# main.net
KiCad netlist of a schematic drawn in EAGLE
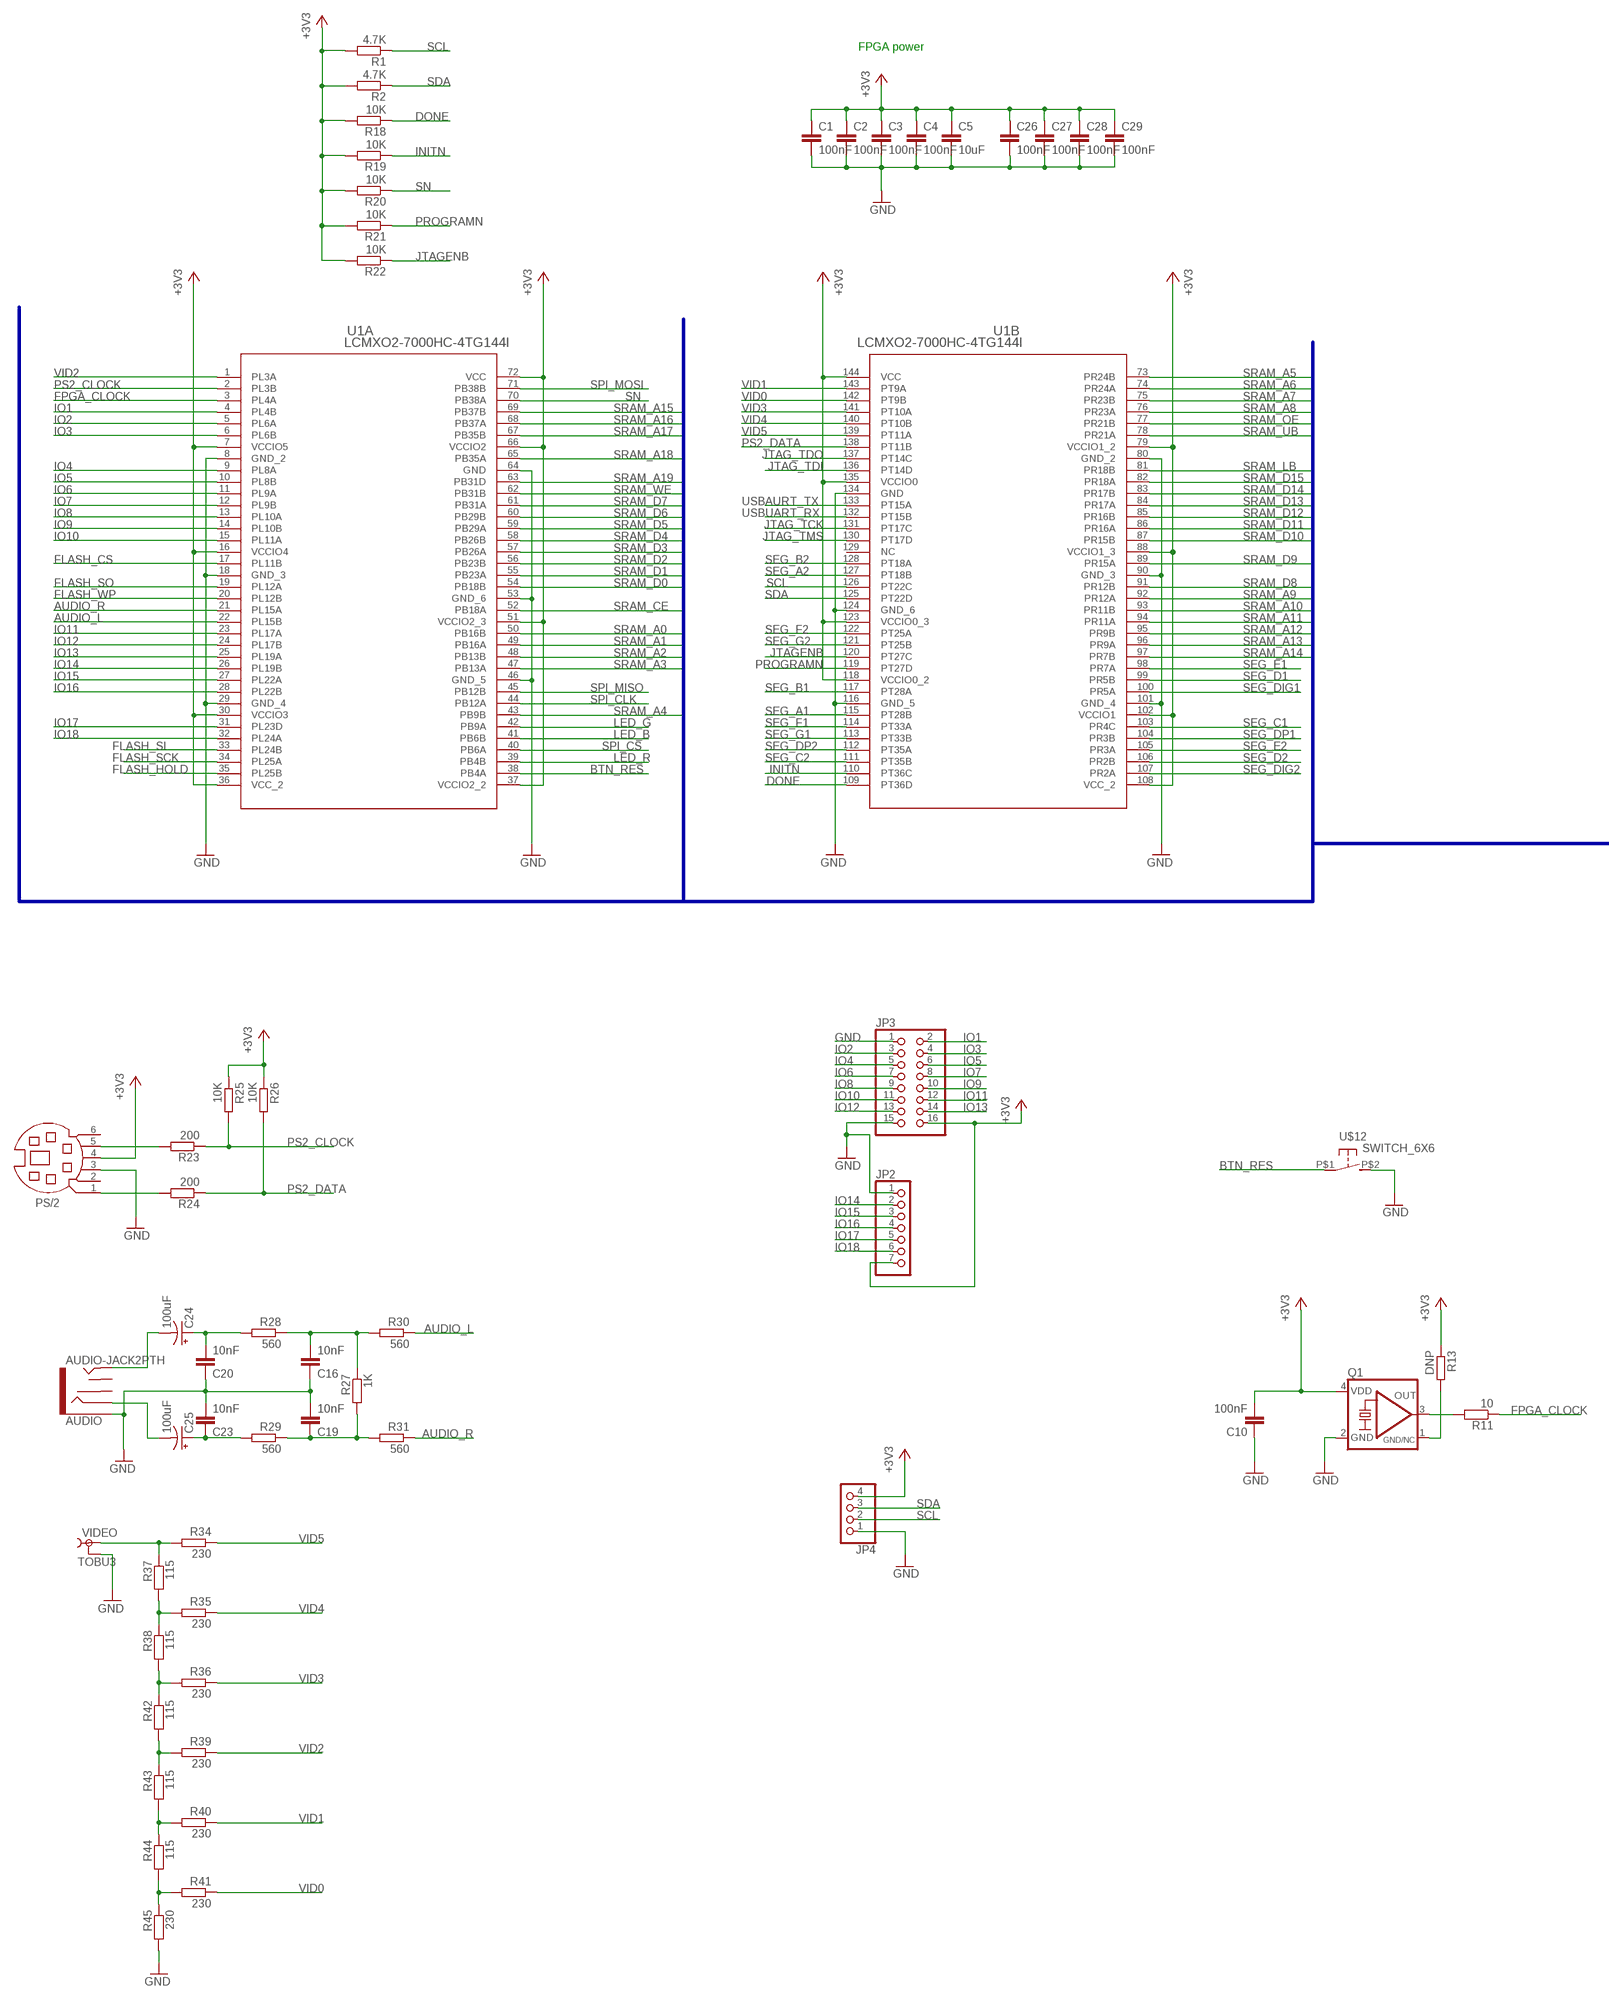
[diagram p0: schematic, sheet 1, part 1 of 2]
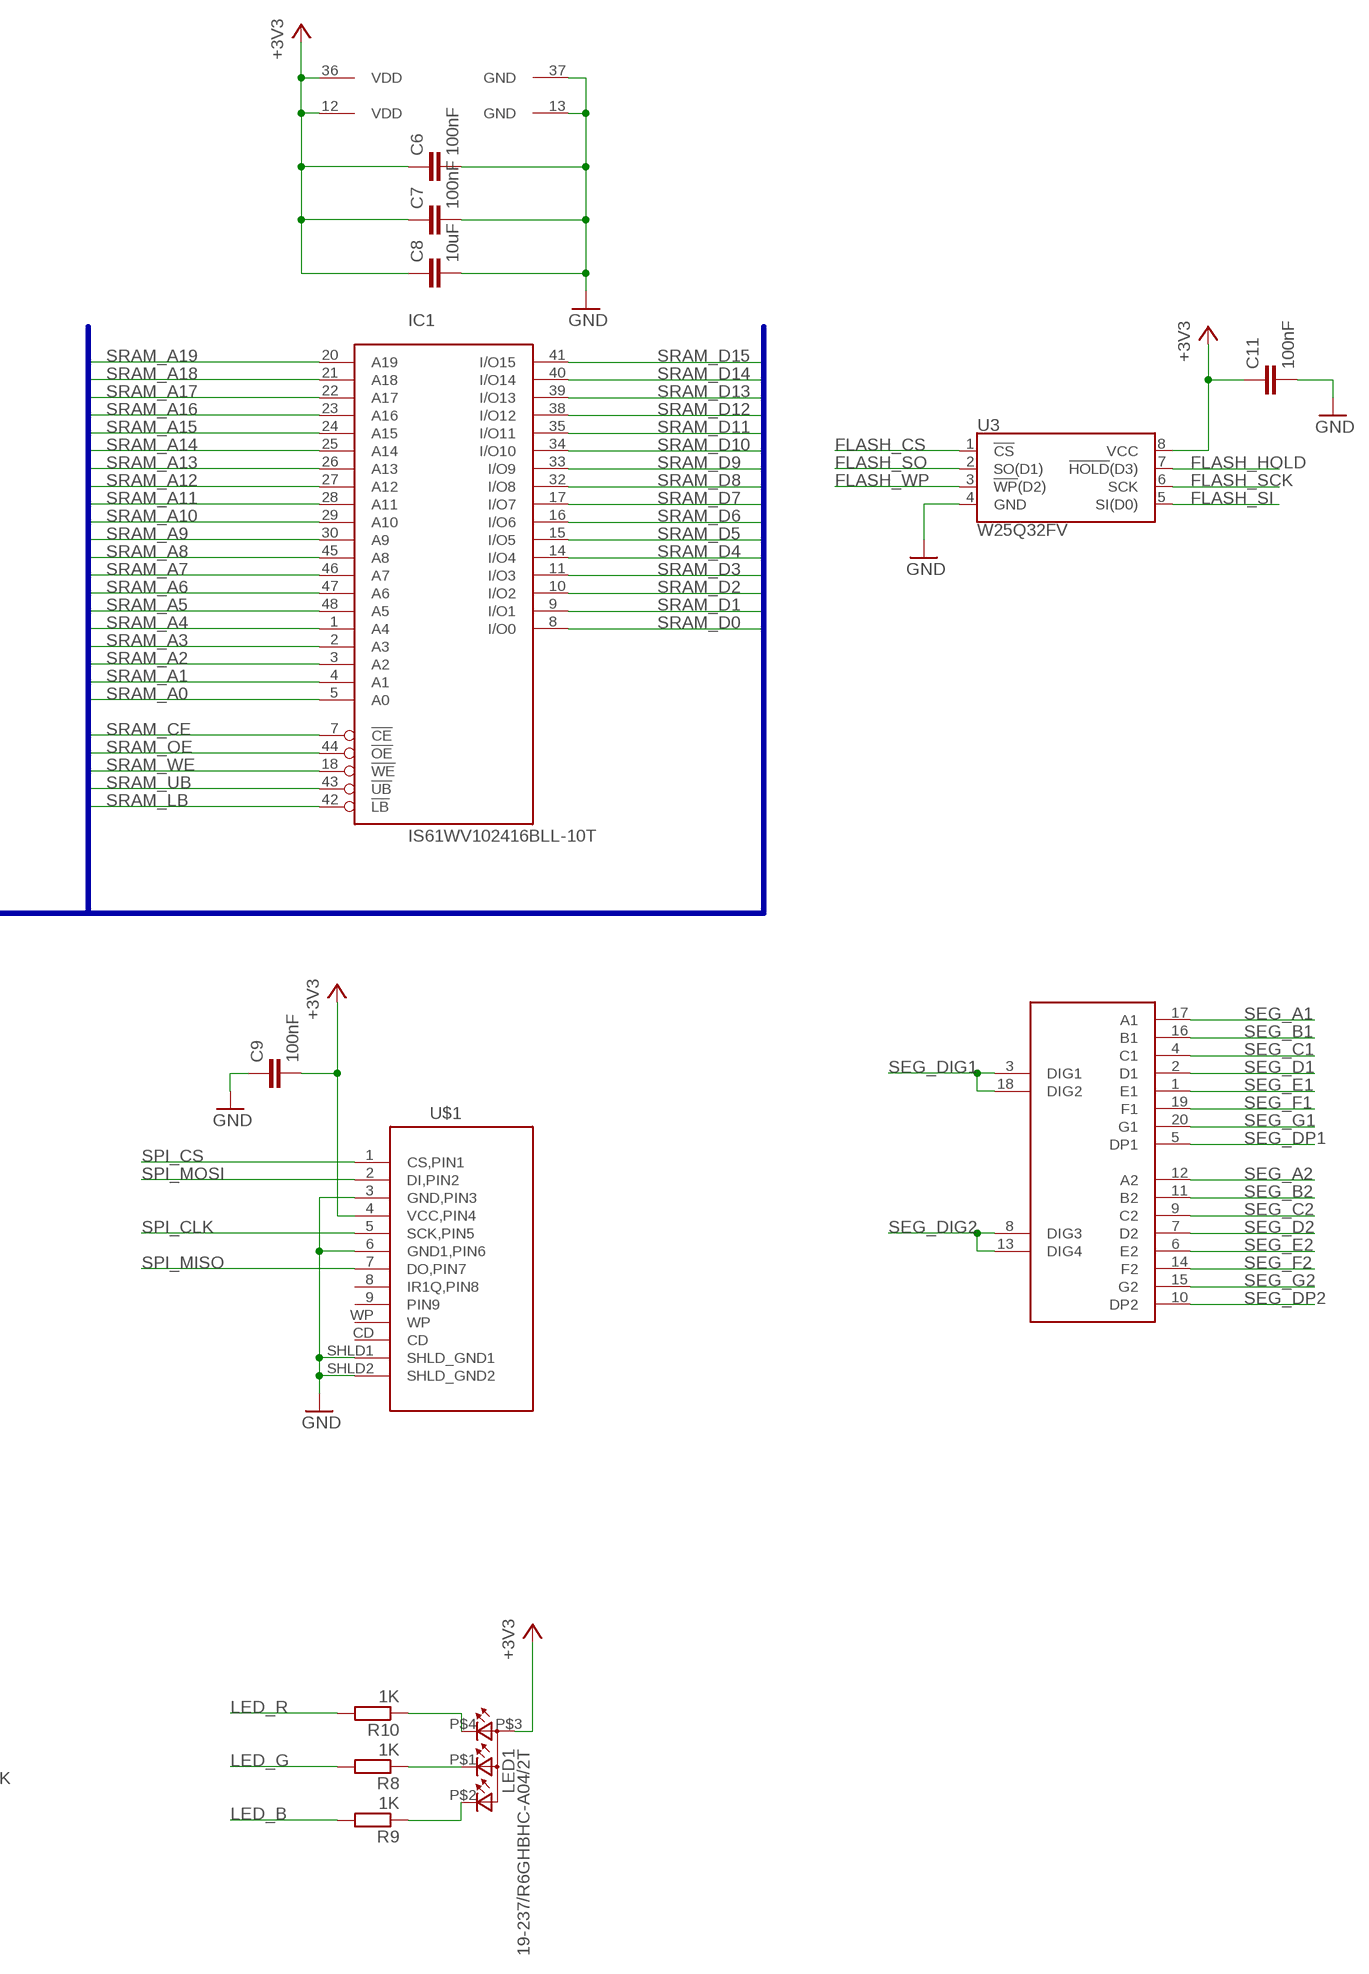
[diagram p1: schematic, sheet 1, part 2 of 2]
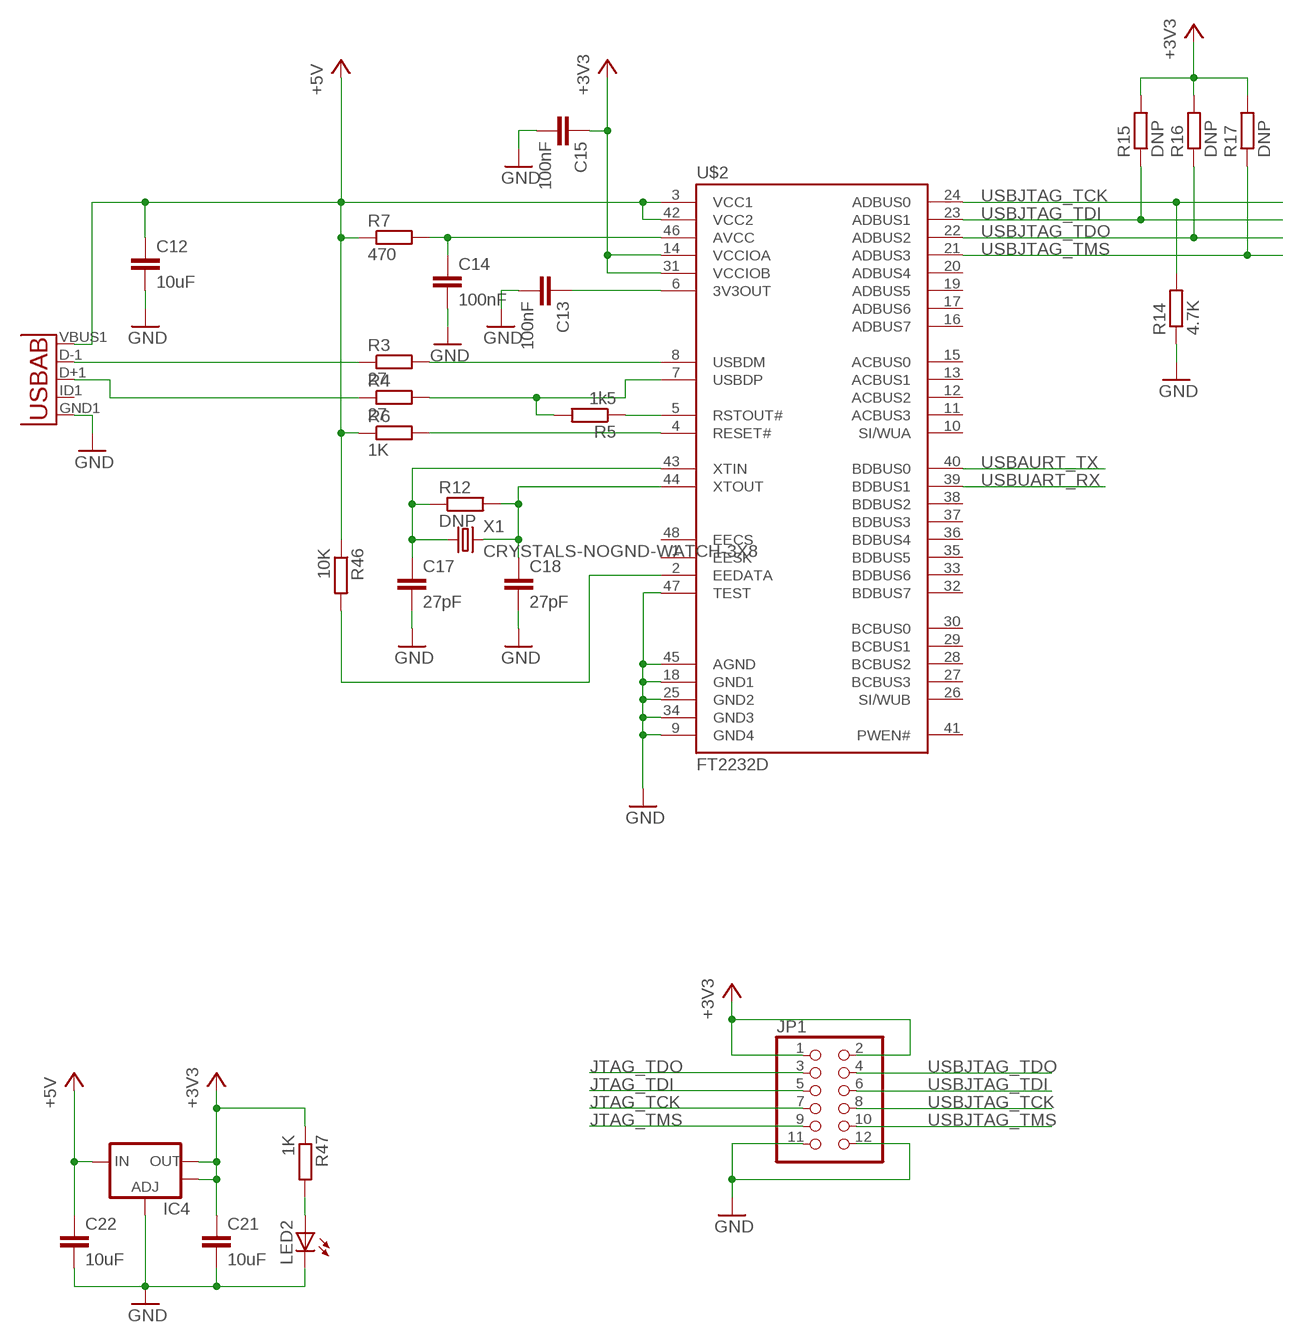
[diagram p2: schematic, sheet 2]

(export (version "E")
  (design (tool "Eeschema 10.0.6"))
  (components
    (comp (ref "AUDIO")
      (value "AUDIO-JACK2PTH")
      (footprint "eagle-import:AUDIO-JACK")
      (libsource (lib "eagle-import") (part "AUDIO-JACK2PTH"))
    )
    (comp (ref "C1")
      (value "100nF")
      (footprint "eagle-import:C0603")
      (libsource (lib "eagle-import") (part "C-EUC0603"))
    )
    (comp (ref "C2")
      (value "100nF")
      (footprint "eagle-import:C0603")
      (libsource (lib "eagle-import") (part "C-EUC0603"))
    )
    (comp (ref "C3")
      (value "100nF")
      (footprint "eagle-import:C0603")
      (libsource (lib "eagle-import") (part "C-EUC0603"))
    )
    (comp (ref "C4")
      (value "100nF")
      (footprint "eagle-import:C0603")
      (libsource (lib "eagle-import") (part "C-EUC0603"))
    )
    (comp (ref "C5")
      (value "10uF")
      (footprint "eagle-import:C0805")
      (libsource (lib "eagle-import") (part "C-EUC0805"))
    )
    (comp (ref "C6")
      (value "100nF")
      (footprint "eagle-import:C0603")
      (libsource (lib "eagle-import") (part "C-EUC0603"))
    )
    (comp (ref "C7")
      (value "100nF")
      (footprint "eagle-import:C0603")
      (libsource (lib "eagle-import") (part "C-EUC0603"))
    )
    (comp (ref "C8")
      (value "10uF")
      (footprint "eagle-import:C0805")
      (libsource (lib "eagle-import") (part "C-EUC0805"))
    )
    (comp (ref "C9")
      (value "100nF")
      (footprint "eagle-import:C0603")
      (libsource (lib "eagle-import") (part "C-EUC0603"))
    )
    (comp (ref "C10")
      (value "100nF")
      (footprint "eagle-import:C0603")
      (libsource (lib "eagle-import") (part "C-EUC0603"))
    )
    (comp (ref "C11")
      (value "100nF")
      (footprint "eagle-import:C0603")
      (libsource (lib "eagle-import") (part "C-EUC0603"))
    )
    (comp (ref "C16")
      (value "10nF")
      (footprint "eagle-import:C0603")
      (libsource (lib "eagle-import") (part "C-EUC0603"))
    )
    (comp (ref "C19")
      (value "10nF")
      (footprint "eagle-import:C0603")
      (libsource (lib "eagle-import") (part "C-EUC0603"))
    )
    (comp (ref "C20")
      (value "10nF")
      (footprint "eagle-import:C0603")
      (libsource (lib "eagle-import") (part "C-EUC0603"))
    )
    (comp (ref "C23")
      (value "10nF")
      (footprint "eagle-import:C0603")
      (libsource (lib "eagle-import") (part "C-EUC0603"))
    )
    (comp (ref "C24")
      (value "100uF")
      (footprint "eagle-import:EIA7343")
      (libsource (lib "eagle-import") (part "CAP_POL7343"))
    )
    (comp (ref "C25")
      (value "100uF")
      (footprint "eagle-import:EIA7343")
      (libsource (lib "eagle-import") (part "CAP_POL7343"))
    )
    (comp (ref "C26")
      (value "100nF")
      (footprint "eagle-import:C0603")
      (libsource (lib "eagle-import") (part "C-EUC0603"))
    )
    (comp (ref "C27")
      (value "100nF")
      (footprint "eagle-import:C0603")
      (libsource (lib "eagle-import") (part "C-EUC0603"))
    )
    (comp (ref "C28")
      (value "100nF")
      (footprint "eagle-import:C0603")
      (libsource (lib "eagle-import") (part "C-EUC0603"))
    )
    (comp (ref "C29")
      (value "100nF")
      (footprint "eagle-import:C0603")
      (libsource (lib "eagle-import") (part "C-EUC0603"))
    )
    (comp (ref "IC1")
      (value "IS61WV102416BLL-10T")
      (footprint "eagle-import:TSOP-I-48-12X40MM")
      (libsource (lib "eagle-import") (part "IS61WV102416BLL-T10"))
    )
    (comp (ref "JP2")
      (value "PINHD-1X7")
      (footprint "eagle-import:1X07")
      (libsource (lib "eagle-import") (part "PINHD-1X7"))
    )
    (comp (ref "JP3")
      (value "PINHD-2X8")
      (footprint "eagle-import:2X08")
      (libsource (lib "eagle-import") (part "PINHD-2X8"))
    )
    (comp (ref "JP4")
      (value "PINHD-1X4")
      (footprint "eagle-import:1X04")
      (libsource (lib "eagle-import") (part "PINHD-1X4"))
    )
    (comp (ref "LED1")
      (value "19-237/R6GHBHC-A04/2T")
      (footprint "eagle-import:19-237_R6GHBHC-A04_2T")
      (libsource (lib "eagle-import") (part "19-237/R6GHBHC-A04/2T"))
    )
    (comp (ref "PS/2")
      (value "MD06SS")
      (footprint "eagle-import:MDIN06SS")
      (libsource (lib "eagle-import") (part "MD06SS"))
    )
    (comp (ref "Q1")
      (value "KXO-TCXO-CMOS-82")
      (footprint "eagle-import:7.0X5.0_KXO-82-TCXO")
      (libsource (lib "eagle-import") (part "KXO-TCXO-CMOS-82"))
    )
    (comp (ref "R1")
      (value "4.7K")
      (footprint "eagle-import:R0603")
      (libsource (lib "eagle-import") (part "R-EU_R0603"))
    )
    (comp (ref "R2")
      (value "4.7K")
      (footprint "eagle-import:R0603")
      (libsource (lib "eagle-import") (part "R-EU_R0603"))
    )
    (comp (ref "R8")
      (value "1K")
      (footprint "eagle-import:R0603")
      (libsource (lib "eagle-import") (part "R-EU_R0603"))
    )
    (comp (ref "R9")
      (value "1K")
      (footprint "eagle-import:R0603")
      (libsource (lib "eagle-import") (part "R-EU_R0603"))
    )
    (comp (ref "R10")
      (value "1K")
      (footprint "eagle-import:R0603")
      (libsource (lib "eagle-import") (part "R-EU_R0603"))
    )
    (comp (ref "R11")
      (value "10")
      (footprint "eagle-import:R0603")
      (libsource (lib "eagle-import") (part "R-EU_R0603"))
    )
    (comp (ref "R13")
      (value "DNP")
      (footprint "eagle-import:R0603")
      (libsource (lib "eagle-import") (part "R-EU_R0603"))
    )
    (comp (ref "R18")
      (value "10K")
      (footprint "eagle-import:R0603")
      (libsource (lib "eagle-import") (part "R-EU_R0603"))
    )
    (comp (ref "R19")
      (value "10K")
      (footprint "eagle-import:R0603")
      (libsource (lib "eagle-import") (part "R-EU_R0603"))
    )
    (comp (ref "R20")
      (value "10K")
      (footprint "eagle-import:R0603")
      (libsource (lib "eagle-import") (part "R-EU_R0603"))
    )
    (comp (ref "R21")
      (value "10K")
      (footprint "eagle-import:R0603")
      (libsource (lib "eagle-import") (part "R-EU_R0603"))
    )
    (comp (ref "R22")
      (value "10K")
      (footprint "eagle-import:R0603")
      (libsource (lib "eagle-import") (part "R-EU_R0603"))
    )
    (comp (ref "R23")
      (value "200")
      (footprint "eagle-import:R0603")
      (libsource (lib "eagle-import") (part "R-EU_R0603"))
    )
    (comp (ref "R24")
      (value "200")
      (footprint "eagle-import:R0603")
      (libsource (lib "eagle-import") (part "R-EU_R0603"))
    )
    (comp (ref "R25")
      (value "10K")
      (footprint "eagle-import:R0603")
      (libsource (lib "eagle-import") (part "R-EU_R0603"))
    )
    (comp (ref "R26")
      (value "10K")
      (footprint "eagle-import:R0603")
      (libsource (lib "eagle-import") (part "R-EU_R0603"))
    )
    (comp (ref "R27")
      (value "1K")
      (footprint "eagle-import:R0603")
      (libsource (lib "eagle-import") (part "R-EU_R0603"))
    )
    (comp (ref "R28")
      (value "560")
      (footprint "eagle-import:R0603")
      (libsource (lib "eagle-import") (part "R-EU_R0603"))
    )
    (comp (ref "R29")
      (value "560")
      (footprint "eagle-import:R0603")
      (libsource (lib "eagle-import") (part "R-EU_R0603"))
    )
    (comp (ref "R30")
      (value "560")
      (footprint "eagle-import:R0603")
      (libsource (lib "eagle-import") (part "R-EU_R0603"))
    )
    (comp (ref "R31")
      (value "560")
      (footprint "eagle-import:R0603")
      (libsource (lib "eagle-import") (part "R-EU_R0603"))
    )
    (comp (ref "R34")
      (value "230")
      (footprint "eagle-import:R0603")
      (libsource (lib "eagle-import") (part "R-EU_R0603"))
    )
    (comp (ref "R35")
      (value "230")
      (footprint "eagle-import:R0603")
      (libsource (lib "eagle-import") (part "R-EU_R0603"))
    )
    (comp (ref "R36")
      (value "230")
      (footprint "eagle-import:R0603")
      (libsource (lib "eagle-import") (part "R-EU_R0603"))
    )
    (comp (ref "R37")
      (value "115")
      (footprint "eagle-import:R0603")
      (libsource (lib "eagle-import") (part "R-EU_R0603"))
    )
    (comp (ref "R38")
      (value "115")
      (footprint "eagle-import:R0603")
      (libsource (lib "eagle-import") (part "R-EU_R0603"))
    )
    (comp (ref "R39")
      (value "230")
      (footprint "eagle-import:R0603")
      (libsource (lib "eagle-import") (part "R-EU_R0603"))
    )
    (comp (ref "R40")
      (value "230")
      (footprint "eagle-import:R0603")
      (libsource (lib "eagle-import") (part "R-EU_R0603"))
    )
    (comp (ref "R41")
      (value "230")
      (footprint "eagle-import:R0603")
      (libsource (lib "eagle-import") (part "R-EU_R0603"))
    )
    (comp (ref "R42")
      (value "115")
      (footprint "eagle-import:R0603")
      (libsource (lib "eagle-import") (part "R-EU_R0603"))
    )
    (comp (ref "R43")
      (value "115")
      (footprint "eagle-import:R0603")
      (libsource (lib "eagle-import") (part "R-EU_R0603"))
    )
    (comp (ref "R44")
      (value "115")
      (footprint "eagle-import:R0603")
      (libsource (lib "eagle-import") (part "R-EU_R0603"))
    )
    (comp (ref "R45")
      (value "230")
      (footprint "eagle-import:R0603")
      (libsource (lib "eagle-import") (part "R-EU_R0603"))
    )
    (comp (ref "U$1")
      (value "FCI_SD_SOCKET")
      (footprint "eagle-import:SD-MMC_SOCKET-PP")
      (fields (field (name "MF") "FCI") (field (name "MPN") "10067847-001RLF"))
      (libsource (lib "eagle-import") (part "FCI_SD_SOCKET"))
    )
    (comp (ref "U$3")
      (value "GS2020CR-G")
      (footprint "eagle-import:GS2020CR")
      (libsource (lib "eagle-import") (part "GS2020CR-G"))
    )
    (comp (ref "U$12")
      (value "SWITCH_6X6")
      (footprint "eagle-import:SWITCH_6X6")
      (libsource (lib "eagle-import") (part "SWITCH_6X6"))
    )
    (comp (ref "U1")
      (value "LCMXO2-7000HC-4TG144I")
      (footprint "eagle-import:TQFP144")
      (fields (field (name "MANUFACTURER_PART_NUMBER") "LCMXO27000HC4TG144I"))
      (libsource (lib "eagle-import") (part "LCMXO2-7000HC-4TG144I"))
    )
    (comp (ref "U3")
      (value "W25Q32FV")
      (footprint "eagle-import:SOIC-8")
      (libsource (lib "eagle-import") (part "W25Q32FVSS"))
    )
    (comp (ref "VIDEO")
      (value "TOBU3")
      (footprint "eagle-import:TOBU3")
      (fields (field (name "MF") "FARNELL") (field (name "MPN") "TOBU 3"))
      (libsource (lib "eagle-import") (part "TOBU3"))
    )
    (comp (ref "C12")
      (value "10uF")
      (footprint "eagle-import:C0805")
      (libsource (lib "eagle-import") (part "C-EUC0805"))
    )
    (comp (ref "C13")
      (value "100nF")
      (footprint "eagle-import:C0603")
      (libsource (lib "eagle-import") (part "C-EUC0603"))
    )
    (comp (ref "C14")
      (value "100nF")
      (footprint "eagle-import:C0603")
      (libsource (lib "eagle-import") (part "C-EUC0603"))
    )
    (comp (ref "C15")
      (value "100nF")
      (footprint "eagle-import:C0603")
      (libsource (lib "eagle-import") (part "C-EUC0603"))
    )
    (comp (ref "C17")
      (value "27pF")
      (footprint "eagle-import:C0603")
      (libsource (lib "eagle-import") (part "C-EUC0603"))
    )
    (comp (ref "C18")
      (value "27pF")
      (footprint "eagle-import:C0603")
      (libsource (lib "eagle-import") (part "C-EUC0603"))
    )
    (comp (ref "C21")
      (value "10uF")
      (footprint "eagle-import:C0805")
      (libsource (lib "eagle-import") (part "C-EUC0805"))
    )
    (comp (ref "C22")
      (value "10uF")
      (footprint "eagle-import:C0805")
      (libsource (lib "eagle-import") (part "C-EUC0805"))
    )
    (comp (ref "IC4")
      (value "V_REG_LM1117SOT223")
      (footprint "eagle-import:SOT223")
      (libsource (lib "eagle-import") (part "V_REG_LM1117SOT223"))
    )
    (comp (ref "JP1")
      (value "PINHD-2X6")
      (footprint "eagle-import:2X06")
      (libsource (lib "eagle-import") (part "PINHD-2X6"))
    )
    (comp (ref "LED2")
      (value "LEDCHIPLED_0603")
      (footprint "eagle-import:CHIPLED_0603")
      (libsource (lib "eagle-import") (part "LEDCHIPLED_0603"))
    )
    (comp (ref "R3")
      (value "27")
      (footprint "eagle-import:R0603")
      (libsource (lib "eagle-import") (part "R-EU_R0603"))
    )
    (comp (ref "R4")
      (value "27")
      (footprint "eagle-import:R0603")
      (libsource (lib "eagle-import") (part "R-EU_R0603"))
    )
    (comp (ref "R5")
      (value "1k5")
      (footprint "eagle-import:R0603")
      (libsource (lib "eagle-import") (part "R-EU_R0603"))
    )
    (comp (ref "R6")
      (value "1K")
      (footprint "eagle-import:R0603")
      (libsource (lib "eagle-import") (part "R-EU_R0603"))
    )
    (comp (ref "R7")
      (value "470")
      (footprint "eagle-import:R0603")
      (libsource (lib "eagle-import") (part "R-EU_R0603"))
    )
    (comp (ref "R12")
      (value "DNP")
      (footprint "eagle-import:R0603")
      (libsource (lib "eagle-import") (part "R-EU_R0603"))
    )
    (comp (ref "R14")
      (value "4.7K")
      (footprint "eagle-import:R0603")
      (libsource (lib "eagle-import") (part "R-EU_R0603"))
    )
    (comp (ref "R15")
      (value "DNP")
      (footprint "eagle-import:R0603")
      (libsource (lib "eagle-import") (part "R-EU_R0603"))
    )
    (comp (ref "R16")
      (value "DNP")
      (footprint "eagle-import:R0603")
      (libsource (lib "eagle-import") (part "R-EU_R0603"))
    )
    (comp (ref "R17")
      (value "DNP")
      (footprint "eagle-import:R0603")
      (libsource (lib "eagle-import") (part "R-EU_R0603"))
    )
    (comp (ref "R46")
      (value "10K")
      (footprint "eagle-import:R0603")
      (libsource (lib "eagle-import") (part "R-EU_R0603"))
    )
    (comp (ref "R47")
      (value "1K")
      (footprint "eagle-import:R0603")
      (libsource (lib "eagle-import") (part "R-EU_R0603"))
    )
    (comp (ref "U$2")
      (value "FT2232D")
      (footprint "eagle-import:LQFP-48")
      (libsource (lib "eagle-import") (part "FT2232D"))
    )
    (comp (ref "U2")
      (value "USB\"\"")
      (footprint "eagle-import:USB-MICRO-SMD")
      (libsource (lib "eagle-import") (part "USB{dblquote}{dblquote}"))
    )
    (comp (ref "X1")
      (value "CRYSTALS-NOGND-WATCH-3X8")
      (footprint "eagle-import:WATCH-3X8")
      (libsource (lib "eagle-import") (part "CRYSTALS-NOGND-WATCH-3X8"))
    )
  )
  (nets
    (net (code "1") (name "+3V3") (class "Default")
      (node (ref "C1") (pin "1") (pinfunction "1_1") (pintype "passive"))
      (node (ref "C10") (pin "2") (pinfunction "2_2") (pintype "passive"))
      (node (ref "C11") (pin "1") (pinfunction "1_1") (pintype "passive"))
      (node (ref "C15") (pin "1") (pinfunction "1_1") (pintype "passive"))
      (node (ref "C2") (pin "1") (pinfunction "1_1") (pintype "passive"))
      (node (ref "C21") (pin "1") (pinfunction "1_1") (pintype "passive"))
      (node (ref "C26") (pin "1") (pinfunction "1_1") (pintype "passive"))
      (node (ref "C27") (pin "1") (pinfunction "1_1") (pintype "passive"))
      (node (ref "C28") (pin "1") (pinfunction "1_1") (pintype "passive"))
      (node (ref "C29") (pin "1") (pinfunction "1_1") (pintype "passive"))
      (node (ref "C3") (pin "1") (pinfunction "1_1") (pintype "passive"))
      (node (ref "C4") (pin "1") (pinfunction "1_1") (pintype "passive"))
      (node (ref "C5") (pin "1") (pinfunction "1_1") (pintype "passive"))
      (node (ref "C6") (pin "1") (pinfunction "1_1") (pintype "passive"))
      (node (ref "C7") (pin "1") (pinfunction "1_1") (pintype "passive"))
      (node (ref "C8") (pin "1") (pinfunction "1_1") (pintype "passive"))
      (node (ref "C9") (pin "2") (pinfunction "2_2") (pintype "passive"))
      (node (ref "IC1") (pin "12") (pinfunction "VDD_12") (pintype "power_in"))
      (node (ref "IC1") (pin "36") (pinfunction "VDD_36") (pintype "power_in"))
      (node (ref "IC4") (pin "2") (pinfunction "OUT_2") (pintype "output"))
      (node (ref "IC4") (pin "4") (pinfunction "OUT_4") (pintype "output"))
      (node (ref "JP1") (pin "1") (pinfunction "1_1") (pintype "passive"))
      (node (ref "JP1") (pin "2") (pinfunction "2_2") (pintype "passive"))
      (node (ref "JP2") (pin "7") (pinfunction "7_7") (pintype "passive"))
      (node (ref "JP3") (pin "16") (pinfunction "16_16") (pintype "passive"))
      (node (ref "JP4") (pin "4") (pinfunction "4_4") (pintype "passive"))
      (node (ref "LED1") (pin "P$3") (pinfunction "A_P$3") (pintype "passive"))
      (node (ref "PS/2") (pin "4") (pinfunction "4_4") (pintype "passive"))
      (node (ref "Q1") (pin "4") (pinfunction "VDD_4") (pintype "power_in"))
      (node (ref "R1") (pin "2") (pinfunction "2_2") (pintype "passive"))
      (node (ref "R13") (pin "1") (pinfunction "1_1") (pintype "passive"))
      (node (ref "R15") (pin "2") (pinfunction "2_2") (pintype "passive"))
      (node (ref "R16") (pin "2") (pinfunction "2_2") (pintype "passive"))
      (node (ref "R17") (pin "2") (pinfunction "2_2") (pintype "passive"))
      (node (ref "R18") (pin "2") (pinfunction "2_2") (pintype "passive"))
      (node (ref "R19") (pin "2") (pinfunction "2_2") (pintype "passive"))
      (node (ref "R2") (pin "2") (pinfunction "2_2") (pintype "passive"))
      (node (ref "R20") (pin "2") (pinfunction "2_2") (pintype "passive"))
      (node (ref "R21") (pin "2") (pinfunction "2_2") (pintype "passive"))
      (node (ref "R22") (pin "2") (pinfunction "2_2") (pintype "passive"))
      (node (ref "R25") (pin "1") (pinfunction "1_1") (pintype "passive"))
      (node (ref "R26") (pin "1") (pinfunction "1_1") (pintype "passive"))
      (node (ref "R47") (pin "1") (pinfunction "1_1") (pintype "passive"))
      (node (ref "U$1") (pin "4") (pinfunction "VCC,PIN4_4") (pintype "bidirectional"))
      (node (ref "U$2") (pin "14") (pinfunction "VCCIOA_14") (pintype "power_in"))
      (node (ref "U$2") (pin "31") (pinfunction "VCCIOB_31") (pintype "bidirectional"))
      (node (ref "U1") (pin "102") (pinfunction "VCCIO1_102") (pintype "power_in"))
      (node (ref "U1") (pin "108") (pinfunction "VCC_2_108") (pintype "power_in"))
      (node (ref "U1") (pin "118") (pinfunction "VCCIO0_2_118") (pintype "power_in"))
      (node (ref "U1") (pin "123") (pinfunction "VCCIO0_3_123") (pintype "power_in"))
      (node (ref "U1") (pin "135") (pinfunction "VCCIO0_135") (pintype "power_in"))
      (node (ref "U1") (pin "144") (pinfunction "VCC_144") (pintype "power_in"))
      (node (ref "U1") (pin "16") (pinfunction "VCCIO4_16") (pintype "power_in"))
      (node (ref "U1") (pin "30") (pinfunction "VCCIO3_30") (pintype "power_in"))
      (node (ref "U1") (pin "36") (pinfunction "VCC_2_36") (pintype "power_in"))
      (node (ref "U1") (pin "37") (pinfunction "VCCIO2_2_37") (pintype "power_in"))
      (node (ref "U1") (pin "51") (pinfunction "VCCIO2_3_51") (pintype "power_in"))
      (node (ref "U1") (pin "66") (pinfunction "VCCIO2_66") (pintype "power_in"))
      (node (ref "U1") (pin "7") (pinfunction "VCCIO5_7") (pintype "power_in"))
      (node (ref "U1") (pin "72") (pinfunction "VCC_72") (pintype "power_in"))
      (node (ref "U1") (pin "79") (pinfunction "VCCIO1_2_79") (pintype "power_in"))
      (node (ref "U1") (pin "88") (pinfunction "VCCIO1_3_88") (pintype "power_in"))
      (node (ref "U3") (pin "8") (pinfunction "VCC_8") (pintype "bidirectional"))
    )
    (net (code "2") (name "+5V") (class "Default")
      (node (ref "C12") (pin "1") (pinfunction "1_1") (pintype "passive"))
      (node (ref "C22") (pin "1") (pinfunction "1_1") (pintype "passive"))
      (node (ref "IC4") (pin "3") (pinfunction "IN_3") (pintype "input"))
      (node (ref "R46") (pin "1") (pinfunction "1_1") (pintype "passive"))
      (node (ref "R6") (pin "1") (pinfunction "1_1") (pintype "passive"))
      (node (ref "R7") (pin "1") (pinfunction "1_1") (pintype "passive"))
      (node (ref "U$2") (pin "3") (pinfunction "VCC1_3") (pintype "power_in"))
      (node (ref "U$2") (pin "42") (pinfunction "VCC2_42") (pintype "power_in"))
      (node (ref "U2") (pin "VBUS1") (pinfunction "VBUS_VBUS1") (pintype "bidirectional"))
    )
    (net (code "3") (name "AUDIO_L") (class "Default")
      (node (ref "R30") (pin "1") (pinfunction "1_1") (pintype "passive"))
      (node (ref "U1") (pin "22") (pinfunction "PL15B_22") (pintype "passive"))
    )
    (net (code "4") (name "AUDIO_R") (class "Default")
      (node (ref "R31") (pin "1") (pinfunction "1_1") (pintype "passive"))
      (node (ref "U1") (pin "21") (pinfunction "PL15A_21") (pintype "passive"))
    )
    (net (code "5") (name "BTN_RES") (class "Default")
      (node (ref "U$12") (pin "P$1") (pinfunction "P_P$1") (pintype "passive"))
      (node (ref "U1") (pin "38") (pinfunction "PB4A_38") (pintype "passive"))
    )
    (net (code "6") (name "DONE") (class "Default")
      (node (ref "R18") (pin "1") (pinfunction "1_1") (pintype "passive"))
      (node (ref "U1") (pin "109") (pinfunction "PT36D_109") (pintype "passive"))
    )
    (net (code "7") (name "FLASH_CS") (class "Default")
      (node (ref "U1") (pin "17") (pinfunction "PL11B_17") (pintype "passive"))
      (node (ref "U3") (pin "1") (pinfunction "~{CS}_1") (pintype "bidirectional"))
    )
    (net (code "8") (name "FLASH_HOLD") (class "Default")
      (node (ref "U1") (pin "35") (pinfunction "PL25B_35") (pintype "passive"))
      (node (ref "U3") (pin "7") (pinfunction "~{HOLD}(D3)_7") (pintype "bidirectional"))
    )
    (net (code "9") (name "FLASH_SCK") (class "Default")
      (node (ref "U1") (pin "34") (pinfunction "PL25A_34") (pintype "passive"))
      (node (ref "U3") (pin "6") (pinfunction "SCK_6") (pintype "bidirectional"))
    )
    (net (code "10") (name "FLASH_SI") (class "Default")
      (node (ref "U1") (pin "33") (pinfunction "PL24B_33") (pintype "passive"))
      (node (ref "U3") (pin "5") (pinfunction "SI(D0)_5") (pintype "bidirectional"))
    )
    (net (code "11") (name "FLASH_SO") (class "Default")
      (node (ref "U1") (pin "19") (pinfunction "PL12A_19") (pintype "passive"))
      (node (ref "U3") (pin "2") (pinfunction "SO(D1)_2") (pintype "bidirectional"))
    )
    (net (code "12") (name "FLASH_WP") (class "Default")
      (node (ref "U1") (pin "20") (pinfunction "PL12B_20") (pintype "passive"))
      (node (ref "U3") (pin "3") (pinfunction "~{WP}(D2)_3") (pintype "bidirectional"))
    )
    (net (code "13") (name "FPGA_CLOCK") (class "Default")
      (node (ref "R11") (pin "1") (pinfunction "1_1") (pintype "passive"))
      (node (ref "U1") (pin "3") (pinfunction "PL4A_3") (pintype "passive"))
    )
    (net (code "14") (name "GND") (class "Default")
      (node (ref "AUDIO") (pin "SLEEVE") (pinfunction "SLEEVE_SLEEVE") (pintype "bidirectional"))
      (node (ref "C1") (pin "2") (pinfunction "2_2") (pintype "passive"))
      (node (ref "C10") (pin "1") (pinfunction "1_1") (pintype "passive"))
      (node (ref "C11") (pin "2") (pinfunction "2_2") (pintype "passive"))
      (node (ref "C12") (pin "2") (pinfunction "2_2") (pintype "passive"))
      (node (ref "C13") (pin "2") (pinfunction "2_2") (pintype "passive"))
      (node (ref "C14") (pin "2") (pinfunction "2_2") (pintype "passive"))
      (node (ref "C15") (pin "2") (pinfunction "2_2") (pintype "passive"))
      (node (ref "C16") (pin "1") (pinfunction "1_1") (pintype "passive"))
      (node (ref "C17") (pin "2") (pinfunction "2_2") (pintype "passive"))
      (node (ref "C18") (pin "2") (pinfunction "2_2") (pintype "passive"))
      (node (ref "C19") (pin "2") (pinfunction "2_2") (pintype "passive"))
      (node (ref "C2") (pin "2") (pinfunction "2_2") (pintype "passive"))
      (node (ref "C20") (pin "1") (pinfunction "1_1") (pintype "passive"))
      (node (ref "C21") (pin "2") (pinfunction "2_2") (pintype "passive"))
      (node (ref "C22") (pin "2") (pinfunction "2_2") (pintype "passive"))
      (node (ref "C23") (pin "2") (pinfunction "2_2") (pintype "passive"))
      (node (ref "C26") (pin "2") (pinfunction "2_2") (pintype "passive"))
      (node (ref "C27") (pin "2") (pinfunction "2_2") (pintype "passive"))
      (node (ref "C28") (pin "2") (pinfunction "2_2") (pintype "passive"))
      (node (ref "C29") (pin "2") (pinfunction "2_2") (pintype "passive"))
      (node (ref "C3") (pin "2") (pinfunction "2_2") (pintype "passive"))
      (node (ref "C4") (pin "2") (pinfunction "2_2") (pintype "passive"))
      (node (ref "C5") (pin "2") (pinfunction "2_2") (pintype "passive"))
      (node (ref "C6") (pin "2") (pinfunction "2_2") (pintype "passive"))
      (node (ref "C7") (pin "2") (pinfunction "2_2") (pintype "passive"))
      (node (ref "C8") (pin "2") (pinfunction "2_2") (pintype "passive"))
      (node (ref "C9") (pin "1") (pinfunction "1_1") (pintype "passive"))
      (node (ref "IC1") (pin "13") (pinfunction "GND_13") (pintype "power_in"))
      (node (ref "IC1") (pin "37") (pinfunction "GND_37") (pintype "power_in"))
      (node (ref "IC4") (pin "1") (pinfunction "ADJ_1") (pintype "input"))
      (node (ref "JP1") (pin "11") (pinfunction "11_11") (pintype "passive"))
      (node (ref "JP1") (pin "12") (pinfunction "12_12") (pintype "passive"))
      (node (ref "JP2") (pin "1") (pinfunction "1_1") (pintype "passive"))
      (node (ref "JP3") (pin "1") (pinfunction "1_1") (pintype "passive"))
      (node (ref "JP3") (pin "15") (pinfunction "15_15") (pintype "passive"))
      (node (ref "JP4") (pin "1") (pinfunction "1_1") (pintype "passive"))
      (node (ref "LED2") (pin "C") (pinfunction "C_C") (pintype "passive"))
      (node (ref "PS/2") (pin "3") (pinfunction "3_3") (pintype "passive"))
      (node (ref "Q1") (pin "2") (pinfunction "GND_2") (pintype "power_in"))
      (node (ref "R14") (pin "1") (pinfunction "1_1") (pintype "passive"))
      (node (ref "R45") (pin "2") (pinfunction "2_2") (pintype "passive"))
      (node (ref "U$1") (pin "3") (pinfunction "GND,PIN3_3") (pintype "bidirectional"))
      (node (ref "U$1") (pin "6") (pinfunction "GND1,PIN6_6") (pintype "bidirectional"))
      (node (ref "U$1") (pin "SHLD1") (pinfunction "SHLD_GND1_SHLD1") (pintype "bidirectional"))
      (node (ref "U$1") (pin "SHLD2") (pinfunction "SHLD_GND2_SHLD2") (pintype "bidirectional"))
      (node (ref "U$12") (pin "P$2") (pinfunction "S_P$2") (pintype "passive"))
      (node (ref "U$2") (pin "18") (pinfunction "GND1_18") (pintype "power_in"))
      (node (ref "U$2") (pin "25") (pinfunction "GND2_25") (pintype "power_in"))
      (node (ref "U$2") (pin "34") (pinfunction "GND3_34") (pintype "power_in"))
      (node (ref "U$2") (pin "45") (pinfunction "AGND_45") (pintype "power_in"))
      (node (ref "U$2") (pin "47") (pinfunction "TEST_47") (pintype "input"))
      (node (ref "U$2") (pin "9") (pinfunction "GND4_9") (pintype "bidirectional"))
      (node (ref "U1") (pin "101") (pinfunction "GND_4_101") (pintype "power_in"))
      (node (ref "U1") (pin "116") (pinfunction "GND_5_116") (pintype "power_in"))
      (node (ref "U1") (pin "124") (pinfunction "GND_6_124") (pintype "power_in"))
      (node (ref "U1") (pin "134") (pinfunction "GND_134") (pintype "power_in"))
      (node (ref "U1") (pin "18") (pinfunction "GND_3_18") (pintype "power_in"))
      (node (ref "U1") (pin "29") (pinfunction "GND_4_29") (pintype "power_in"))
      (node (ref "U1") (pin "46") (pinfunction "GND_5_46") (pintype "power_in"))
      (node (ref "U1") (pin "53") (pinfunction "GND_6_53") (pintype "power_in"))
      (node (ref "U1") (pin "64") (pinfunction "GND_64") (pintype "power_in"))
      (node (ref "U1") (pin "8") (pinfunction "GND_2_8") (pintype "power_in"))
      (node (ref "U1") (pin "80") (pinfunction "GND_2_80") (pintype "power_in"))
      (node (ref "U1") (pin "90") (pinfunction "GND_3_90") (pintype "power_in"))
      (node (ref "U2") (pin "GND1") (pinfunction "GND_GND1") (pintype "bidirectional"))
      (node (ref "U3") (pin "4") (pinfunction "GND_4") (pintype "bidirectional"))
      (node (ref "VIDEO") (pin "2") (pinfunction "2_2") (pintype "passive"))
      (node (ref "VIDEO") (pin "2@1") (pinfunction "2_2@1") (pintype "passive"))
      (node (ref "VIDEO") (pin "2@2") (pinfunction "2_2@2") (pintype "passive"))
    )
    (net (code "15") (name "INITN") (class "Default")
      (node (ref "R19") (pin "1") (pinfunction "1_1") (pintype "passive"))
      (node (ref "U1") (pin "110") (pinfunction "PT36C_110") (pintype "passive"))
    )
    (net (code "16") (name "IO1") (class "Default")
      (node (ref "JP3") (pin "2") (pinfunction "2_2") (pintype "passive"))
      (node (ref "U1") (pin "4") (pinfunction "PL4B_4") (pintype "passive"))
    )
    (net (code "17") (name "IO2") (class "Default")
      (node (ref "JP3") (pin "3") (pinfunction "3_3") (pintype "passive"))
      (node (ref "U1") (pin "5") (pinfunction "PL6A_5") (pintype "passive"))
    )
    (net (code "18") (name "IO3") (class "Default")
      (node (ref "JP3") (pin "4") (pinfunction "4_4") (pintype "passive"))
      (node (ref "U1") (pin "6") (pinfunction "PL6B_6") (pintype "passive"))
    )
    (net (code "19") (name "IO4") (class "Default")
      (node (ref "JP3") (pin "5") (pinfunction "5_5") (pintype "passive"))
      (node (ref "U1") (pin "9") (pinfunction "PL8A_9") (pintype "passive"))
    )
    (net (code "20") (name "IO5") (class "Default")
      (node (ref "JP3") (pin "6") (pinfunction "6_6") (pintype "passive"))
      (node (ref "U1") (pin "10") (pinfunction "PL8B_10") (pintype "passive"))
    )
    (net (code "21") (name "IO6") (class "Default")
      (node (ref "JP3") (pin "7") (pinfunction "7_7") (pintype "passive"))
      (node (ref "U1") (pin "11") (pinfunction "PL9A_11") (pintype "passive"))
    )
    (net (code "22") (name "IO7") (class "Default")
      (node (ref "JP3") (pin "8") (pinfunction "8_8") (pintype "passive"))
      (node (ref "U1") (pin "12") (pinfunction "PL9B_12") (pintype "passive"))
    )
    (net (code "23") (name "IO8") (class "Default")
      (node (ref "JP3") (pin "9") (pinfunction "9_9") (pintype "passive"))
      (node (ref "U1") (pin "13") (pinfunction "PL10A_13") (pintype "passive"))
    )
    (net (code "24") (name "IO9") (class "Default")
      (node (ref "JP3") (pin "10") (pinfunction "10_10") (pintype "passive"))
      (node (ref "U1") (pin "14") (pinfunction "PL10B_14") (pintype "passive"))
    )
    (net (code "25") (name "IO10") (class "Default")
      (node (ref "JP3") (pin "11") (pinfunction "11_11") (pintype "passive"))
      (node (ref "U1") (pin "15") (pinfunction "PL11A_15") (pintype "passive"))
    )
    (net (code "26") (name "IO11") (class "Default")
      (node (ref "JP3") (pin "12") (pinfunction "12_12") (pintype "passive"))
      (node (ref "U1") (pin "23") (pinfunction "PL17A_23") (pintype "passive"))
    )
    (net (code "27") (name "IO12") (class "Default")
      (node (ref "JP3") (pin "13") (pinfunction "13_13") (pintype "passive"))
      (node (ref "U1") (pin "24") (pinfunction "PL17B_24") (pintype "passive"))
    )
    (net (code "28") (name "IO13") (class "Default")
      (node (ref "JP3") (pin "14") (pinfunction "14_14") (pintype "passive"))
      (node (ref "U1") (pin "25") (pinfunction "PL19A_25") (pintype "passive"))
    )
    (net (code "29") (name "IO14") (class "Default")
      (node (ref "JP2") (pin "2") (pinfunction "2_2") (pintype "passive"))
      (node (ref "U1") (pin "26") (pinfunction "PL19B_26") (pintype "passive"))
    )
    (net (code "30") (name "IO15") (class "Default")
      (node (ref "JP2") (pin "3") (pinfunction "3_3") (pintype "passive"))
      (node (ref "U1") (pin "27") (pinfunction "PL22A_27") (pintype "passive"))
    )
    (net (code "31") (name "IO16") (class "Default")
      (node (ref "JP2") (pin "4") (pinfunction "4_4") (pintype "passive"))
      (node (ref "U1") (pin "28") (pinfunction "PL22B_28") (pintype "passive"))
    )
    (net (code "32") (name "IO17") (class "Default")
      (node (ref "JP2") (pin "5") (pinfunction "5_5") (pintype "passive"))
      (node (ref "U1") (pin "31") (pinfunction "PL23D_31") (pintype "passive"))
    )
    (net (code "33") (name "IO18") (class "Default")
      (node (ref "JP2") (pin "6") (pinfunction "6_6") (pintype "passive"))
      (node (ref "U1") (pin "32") (pinfunction "PL24A_32") (pintype "passive"))
    )
    (net (code "34") (name "JTAGENB") (class "Default")
      (node (ref "R22") (pin "1") (pinfunction "1_1") (pintype "passive"))
      (node (ref "U1") (pin "120") (pinfunction "PT27C_120") (pintype "passive"))
    )
    (net (code "35") (name "JTAG_TCK") (class "Default")
      (node (ref "JP1") (pin "7") (pinfunction "7_7") (pintype "passive"))
      (node (ref "U1") (pin "131") (pinfunction "PT17C_131") (pintype "passive"))
    )
    (net (code "36") (name "JTAG_TDI") (class "Default")
      (node (ref "JP1") (pin "5") (pinfunction "5_5") (pintype "passive"))
      (node (ref "U1") (pin "136") (pinfunction "PT14D_136") (pintype "passive"))
    )
    (net (code "37") (name "JTAG_TDO") (class "Default")
      (node (ref "JP1") (pin "3") (pinfunction "3_3") (pintype "passive"))
      (node (ref "U1") (pin "137") (pinfunction "PT14C_137") (pintype "passive"))
    )
    (net (code "38") (name "JTAG_TMS") (class "Default")
      (node (ref "JP1") (pin "9") (pinfunction "9_9") (pintype "passive"))
      (node (ref "U1") (pin "130") (pinfunction "PT17D_130") (pintype "passive"))
    )
    (net (code "39") (name "LED_B") (class "Default")
      (node (ref "R9") (pin "2") (pinfunction "2_2") (pintype "passive"))
      (node (ref "U1") (pin "41") (pinfunction "PB6B_41") (pintype "passive"))
    )
    (net (code "40") (name "LED_G") (class "Default")
      (node (ref "R8") (pin "2") (pinfunction "2_2") (pintype "passive"))
      (node (ref "U1") (pin "42") (pinfunction "PB9A_42") (pintype "passive"))
    )
    (net (code "41") (name "LED_R") (class "Default")
      (node (ref "R10") (pin "2") (pinfunction "2_2") (pintype "passive"))
      (node (ref "U1") (pin "39") (pinfunction "PB4B_39") (pintype "passive"))
    )
    (net (code "42") (name "Net-(C16-Pad2)") (class "Default")
      (node (ref "C16") (pin "2") (pinfunction "2_2") (pintype "passive"))
      (node (ref "R27") (pin "1") (pinfunction "1_1") (pintype "passive"))
      (node (ref "R28") (pin "1") (pinfunction "1_1") (pintype "passive"))
      (node (ref "R30") (pin "2") (pinfunction "2_2") (pintype "passive"))
    )
    (net (code "43") (name "Net-(C19-Pad1)") (class "Default")
      (node (ref "C19") (pin "1") (pinfunction "1_1") (pintype "passive"))
      (node (ref "R27") (pin "2") (pinfunction "2_2") (pintype "passive"))
      (node (ref "R29") (pin "1") (pinfunction "1_1") (pintype "passive"))
      (node (ref "R31") (pin "2") (pinfunction "2_2") (pintype "passive"))
    )
    (net (code "44") (name "Net-(C24-+)") (class "Default")
      (node (ref "C20") (pin "2") (pinfunction "2_2") (pintype "passive"))
      (node (ref "C24") (pin "A") (pinfunction "+_A") (pintype "passive"))
      (node (ref "R28") (pin "2") (pinfunction "2_2") (pintype "passive"))
    )
    (net (code "45") (name "Net-(C24--)") (class "Default")
      (node (ref "AUDIO") (pin "TIP") (pinfunction "TIP_TIP") (pintype "bidirectional"))
      (node (ref "C24") (pin "C") (pinfunction "-_C") (pintype "passive"))
    )
    (net (code "46") (name "Net-(C25-+)") (class "Default")
      (node (ref "C23") (pin "1") (pinfunction "1_1") (pintype "passive"))
      (node (ref "C25") (pin "A") (pinfunction "+_A") (pintype "passive"))
      (node (ref "R29") (pin "2") (pinfunction "2_2") (pintype "passive"))
    )
    (net (code "47") (name "Net-(C25--)") (class "Default")
      (node (ref "AUDIO") (pin "RING") (pinfunction "RING_RING") (pintype "bidirectional"))
      (node (ref "C25") (pin "C") (pinfunction "-_C") (pintype "passive"))
    )
    (net (code "48") (name "Net-(LED1-CBLUE)") (class "Default")
      (node (ref "LED1") (pin "P$1") (pinfunction "CBLUE_P$1") (pintype "passive"))
      (node (ref "R8") (pin "1") (pinfunction "1_1") (pintype "passive"))
    )
    (net (code "49") (name "Net-(LED1-CGREEN)") (class "Default")
      (node (ref "LED1") (pin "P$2") (pinfunction "CGREEN_P$2") (pintype "passive"))
      (node (ref "R9") (pin "1") (pinfunction "1_1") (pintype "passive"))
    )
    (net (code "50") (name "Net-(LED1-CRED)") (class "Default")
      (node (ref "LED1") (pin "P$4") (pinfunction "CRED_P$4") (pintype "passive"))
      (node (ref "R10") (pin "1") (pinfunction "1_1") (pintype "passive"))
    )
    (net (code "51") (name "Net-(LED2-PadA)") (class "Default")
      (node (ref "LED2") (pin "A") (pinfunction "A_A") (pintype "passive"))
      (node (ref "R47") (pin "2") (pinfunction "2_2") (pintype "passive"))
    )
    (net (code "52") (name "Net-(PS/2-Pad1)") (class "Default")
      (node (ref "PS/2") (pin "1") (pinfunction "1_1") (pintype "passive"))
      (node (ref "R24") (pin "2") (pinfunction "2_2") (pintype "passive"))
    )
    (net (code "53") (name "Net-(PS/2-Pad5)") (class "Default")
      (node (ref "PS/2") (pin "5") (pinfunction "5_5") (pintype "passive"))
      (node (ref "R23") (pin "2") (pinfunction "2_2") (pintype "passive"))
    )
    (net (code "54") (name "Net-(Q1-GND{slash}NC)") (class "Default")
      (node (ref "Q1") (pin "1") (pinfunction "GND/NC_1") (pintype "power_in"))
      (node (ref "R13") (pin "2") (pinfunction "2_2") (pintype "passive"))
    )
    (net (code "55") (name "Net-(Q1-OUT)") (class "Default")
      (node (ref "Q1") (pin "3") (pinfunction "OUT_3") (pintype "output"))
      (node (ref "R11") (pin "2") (pinfunction "2_2") (pintype "passive"))
    )
    (net (code "56") (name "Net-(R34-Pad2)") (class "Default")
      (node (ref "R34") (pin "2") (pinfunction "2_2") (pintype "passive"))
      (node (ref "R37") (pin "1") (pinfunction "1_1") (pintype "passive"))
      (node (ref "VIDEO") (pin "1") (pinfunction "1_1") (pintype "passive"))
    )
    (net (code "57") (name "Net-(R35-Pad2)") (class "Default")
      (node (ref "R35") (pin "2") (pinfunction "2_2") (pintype "passive"))
      (node (ref "R37") (pin "2") (pinfunction "2_2") (pintype "passive"))
      (node (ref "R38") (pin "1") (pinfunction "1_1") (pintype "passive"))
    )
    (net (code "58") (name "Net-(R36-Pad2)") (class "Default")
      (node (ref "R36") (pin "2") (pinfunction "2_2") (pintype "passive"))
      (node (ref "R38") (pin "2") (pinfunction "2_2") (pintype "passive"))
      (node (ref "R42") (pin "1") (pinfunction "1_1") (pintype "passive"))
    )
    (net (code "59") (name "Net-(R39-Pad2)") (class "Default")
      (node (ref "R39") (pin "2") (pinfunction "2_2") (pintype "passive"))
      (node (ref "R42") (pin "2") (pinfunction "2_2") (pintype "passive"))
      (node (ref "R43") (pin "1") (pinfunction "1_1") (pintype "passive"))
    )
    (net (code "60") (name "Net-(R40-Pad2)") (class "Default")
      (node (ref "R40") (pin "2") (pinfunction "2_2") (pintype "passive"))
      (node (ref "R43") (pin "2") (pinfunction "2_2") (pintype "passive"))
      (node (ref "R44") (pin "1") (pinfunction "1_1") (pintype "passive"))
    )
    (net (code "61") (name "Net-(R41-Pad2)") (class "Default")
      (node (ref "R41") (pin "2") (pinfunction "2_2") (pintype "passive"))
      (node (ref "R44") (pin "2") (pinfunction "2_2") (pintype "passive"))
      (node (ref "R45") (pin "1") (pinfunction "1_1") (pintype "passive"))
    )
    (net (code "62") (name "Net-(U$2-3V3OUT)") (class "Default")
      (node (ref "C13") (pin "1") (pinfunction "1_1") (pintype "passive"))
      (node (ref "U$2") (pin "6") (pinfunction "3V3OUT_6") (pintype "output"))
    )
    (net (code "63") (name "Net-(U$2-AVCC)") (class "Default")
      (node (ref "C14") (pin "1") (pinfunction "1_1") (pintype "passive"))
      (node (ref "R7") (pin "2") (pinfunction "2_2") (pintype "passive"))
      (node (ref "U$2") (pin "46") (pinfunction "AVCC_46") (pintype "bidirectional"))
    )
    (net (code "64") (name "Net-(U$2-EEDATA)") (class "Default")
      (node (ref "R46") (pin "2") (pinfunction "2_2") (pintype "passive"))
      (node (ref "U$2") (pin "2") (pinfunction "EEDATA_2") (pintype "bidirectional"))
    )
    (net (code "65") (name "Net-(U$2-RESET#)") (class "Default")
      (node (ref "R6") (pin "2") (pinfunction "2_2") (pintype "passive"))
      (node (ref "U$2") (pin "4") (pinfunction "RESET#_4") (pintype "bidirectional"))
    )
    (net (code "66") (name "Net-(U$2-RSTOUT#)") (class "Default")
      (node (ref "R5") (pin "1") (pinfunction "1_1") (pintype "passive"))
      (node (ref "U$2") (pin "5") (pinfunction "RSTOUT#_5") (pintype "bidirectional"))
    )
    (net (code "67") (name "Net-(U$2-USBDM)") (class "Default")
      (node (ref "R3") (pin "2") (pinfunction "2_2") (pintype "passive"))
      (node (ref "U$2") (pin "8") (pinfunction "USBDM_8") (pintype "bidirectional"))
    )
    (net (code "68") (name "Net-(U$2-USBDP)") (class "Default")
      (node (ref "R4") (pin "2") (pinfunction "2_2") (pintype "passive"))
      (node (ref "R5") (pin "2") (pinfunction "2_2") (pintype "passive"))
      (node (ref "U$2") (pin "7") (pinfunction "USBDP_7") (pintype "bidirectional"))
    )
    (net (code "69") (name "Net-(U$2-XTIN)") (class "Default")
      (node (ref "C17") (pin "1") (pinfunction "1_1") (pintype "passive"))
      (node (ref "R12") (pin "1") (pinfunction "1_1") (pintype "passive"))
      (node (ref "U$2") (pin "43") (pinfunction "XTIN_43") (pintype "bidirectional"))
      (node (ref "X1") (pin "1") (pinfunction "1_1") (pintype "passive"))
    )
    (net (code "70") (name "Net-(U$2-XTOUT)") (class "Default")
      (node (ref "C18") (pin "1") (pinfunction "1_1") (pintype "passive"))
      (node (ref "R12") (pin "2") (pinfunction "2_2") (pintype "passive"))
      (node (ref "U$2") (pin "44") (pinfunction "XTOUT_44") (pintype "bidirectional"))
      (node (ref "X1") (pin "2") (pinfunction "2_2") (pintype "passive"))
    )
    (net (code "71") (name "Net-(U2-D+)") (class "Default")
      (node (ref "R4") (pin "1") (pinfunction "1_1") (pintype "passive"))
      (node (ref "U2") (pin "D+1") (pinfunction "D+_D+1") (pintype "bidirectional"))
    )
    (net (code "72") (name "Net-(U2-D-)") (class "Default")
      (node (ref "R3") (pin "1") (pinfunction "1_1") (pintype "passive"))
      (node (ref "U2") (pin "D-1") (pinfunction "D-_D-1") (pintype "bidirectional"))
    )
    (net (code "73") (name "PROGRAMN") (class "Default")
      (node (ref "R21") (pin "1") (pinfunction "1_1") (pintype "passive"))
      (node (ref "U1") (pin "119") (pinfunction "PT27D_119") (pintype "passive"))
    )
    (net (code "74") (name "PS2_CLOCK") (class "Default")
      (node (ref "R23") (pin "1") (pinfunction "1_1") (pintype "passive"))
      (node (ref "R25") (pin "2") (pinfunction "2_2") (pintype "passive"))
      (node (ref "U1") (pin "2") (pinfunction "PL3B_2") (pintype "passive"))
    )
    (net (code "75") (name "PS2_DATA") (class "Default")
      (node (ref "R24") (pin "1") (pinfunction "1_1") (pintype "passive"))
      (node (ref "R26") (pin "2") (pinfunction "2_2") (pintype "passive"))
      (node (ref "U1") (pin "138") (pinfunction "PT11B_138") (pintype "passive"))
    )
    (net (code "76") (name "SCL") (class "Default")
      (node (ref "JP4") (pin "2") (pinfunction "2_2") (pintype "passive"))
      (node (ref "R1") (pin "1") (pinfunction "1_1") (pintype "passive"))
      (node (ref "U1") (pin "126") (pinfunction "PT22C_126") (pintype "passive"))
    )
    (net (code "77") (name "SDA") (class "Default")
      (node (ref "JP4") (pin "3") (pinfunction "3_3") (pintype "passive"))
      (node (ref "R2") (pin "1") (pinfunction "1_1") (pintype "passive"))
      (node (ref "U1") (pin "125") (pinfunction "PT22D_125") (pintype "passive"))
    )
    (net (code "78") (name "SEG_A1") (class "Default")
      (node (ref "U$3") (pin "17") (pinfunction "A1_17") (pintype "bidirectional"))
      (node (ref "U1") (pin "115") (pinfunction "PT28B_115") (pintype "passive"))
    )
    (net (code "79") (name "SEG_A2") (class "Default")
      (node (ref "U$3") (pin "12") (pinfunction "A2_12") (pintype "bidirectional"))
      (node (ref "U1") (pin "127") (pinfunction "PT18B_127") (pintype "passive"))
    )
    (net (code "80") (name "SEG_B1") (class "Default")
      (node (ref "U$3") (pin "16") (pinfunction "B1_16") (pintype "bidirectional"))
      (node (ref "U1") (pin "117") (pinfunction "PT28A_117") (pintype "passive"))
    )
    (net (code "81") (name "SEG_B2") (class "Default")
      (node (ref "U$3") (pin "11") (pinfunction "B2_11") (pintype "bidirectional"))
      (node (ref "U1") (pin "128") (pinfunction "PT18A_128") (pintype "passive"))
    )
    (net (code "82") (name "SEG_C1") (class "Default")
      (node (ref "U$3") (pin "4") (pinfunction "C1_4") (pintype "bidirectional"))
      (node (ref "U1") (pin "103") (pinfunction "PR4C_103") (pintype "passive"))
    )
    (net (code "83") (name "SEG_C2") (class "Default")
      (node (ref "U$3") (pin "9") (pinfunction "C2_9") (pintype "bidirectional"))
      (node (ref "U1") (pin "111") (pinfunction "PT35B_111") (pintype "passive"))
    )
    (net (code "84") (name "SEG_D1") (class "Default")
      (node (ref "U$3") (pin "2") (pinfunction "D1_2") (pintype "bidirectional"))
      (node (ref "U1") (pin "99") (pinfunction "PR5B_99") (pintype "passive"))
    )
    (net (code "85") (name "SEG_D2") (class "Default")
      (node (ref "U$3") (pin "7") (pinfunction "D2_7") (pintype "bidirectional"))
      (node (ref "U1") (pin "106") (pinfunction "PR2B_106") (pintype "passive"))
    )
    (net (code "86") (name "SEG_DIG1") (class "Default")
      (node (ref "U$3") (pin "18") (pinfunction "DIG2_18") (pintype "bidirectional"))
      (node (ref "U$3") (pin "3") (pinfunction "DIG1_3") (pintype "bidirectional"))
      (node (ref "U1") (pin "100") (pinfunction "PR5A_100") (pintype "passive"))
    )
    (net (code "87") (name "SEG_DIG2") (class "Default")
      (node (ref "U$3") (pin "13") (pinfunction "DIG4_13") (pintype "bidirectional"))
      (node (ref "U$3") (pin "8") (pinfunction "DIG3_8") (pintype "bidirectional"))
      (node (ref "U1") (pin "107") (pinfunction "PR2A_107") (pintype "passive"))
    )
    (net (code "88") (name "SEG_DP1") (class "Default")
      (node (ref "U$3") (pin "5") (pinfunction "DP1_5") (pintype "bidirectional"))
      (node (ref "U1") (pin "104") (pinfunction "PR3B_104") (pintype "passive"))
    )
    (net (code "89") (name "SEG_DP2") (class "Default")
      (node (ref "U$3") (pin "10") (pinfunction "DP2_10") (pintype "bidirectional"))
      (node (ref "U1") (pin "112") (pinfunction "PT35A_112") (pintype "passive"))
    )
    (net (code "90") (name "SEG_E1") (class "Default")
      (node (ref "U$3") (pin "1") (pinfunction "E1_1") (pintype "bidirectional"))
      (node (ref "U1") (pin "98") (pinfunction "PR7A_98") (pintype "passive"))
    )
    (net (code "91") (name "SEG_E2") (class "Default")
      (node (ref "U$3") (pin "6") (pinfunction "E2_6") (pintype "bidirectional"))
      (node (ref "U1") (pin "105") (pinfunction "PR3A_105") (pintype "passive"))
    )
    (net (code "92") (name "SEG_F1") (class "Default")
      (node (ref "U$3") (pin "19") (pinfunction "F1_19") (pintype "bidirectional"))
      (node (ref "U1") (pin "114") (pinfunction "PT33A_114") (pintype "passive"))
    )
    (net (code "93") (name "SEG_F2") (class "Default")
      (node (ref "U$3") (pin "14") (pinfunction "F2_14") (pintype "bidirectional"))
      (node (ref "U1") (pin "122") (pinfunction "PT25A_122") (pintype "passive"))
    )
    (net (code "94") (name "SEG_G1") (class "Default")
      (node (ref "U$3") (pin "20") (pinfunction "G1_20") (pintype "bidirectional"))
      (node (ref "U1") (pin "113") (pinfunction "PT33B_113") (pintype "passive"))
    )
    (net (code "95") (name "SEG_G2") (class "Default")
      (node (ref "U$3") (pin "15") (pinfunction "G2_15") (pintype "bidirectional"))
      (node (ref "U1") (pin "121") (pinfunction "PT25B_121") (pintype "passive"))
    )
    (net (code "96") (name "SN") (class "Default")
      (node (ref "R20") (pin "1") (pinfunction "1_1") (pintype "passive"))
      (node (ref "U1") (pin "70") (pinfunction "PB38A_70") (pintype "passive"))
    )
    (net (code "97") (name "SPI_CLK") (class "Default")
      (node (ref "U$1") (pin "5") (pinfunction "SCK,PIN5_5") (pintype "bidirectional"))
      (node (ref "U1") (pin "44") (pinfunction "PB12A_44") (pintype "passive"))
    )
    (net (code "98") (name "SPI_CS") (class "Default")
      (node (ref "U$1") (pin "1") (pinfunction "CS,PIN1_1") (pintype "bidirectional"))
      (node (ref "U1") (pin "40") (pinfunction "PB6A_40") (pintype "passive"))
    )
    (net (code "99") (name "SPI_MISO") (class "Default")
      (node (ref "U$1") (pin "7") (pinfunction "DO,PIN7_7") (pintype "bidirectional"))
      (node (ref "U1") (pin "45") (pinfunction "PB12B_45") (pintype "passive"))
    )
    (net (code "100") (name "SPI_MOSI") (class "Default")
      (node (ref "U$1") (pin "2") (pinfunction "DI,PIN2_2") (pintype "bidirectional"))
      (node (ref "U1") (pin "71") (pinfunction "PB38B_71") (pintype "passive"))
    )
    (net (code "101") (name "SRAM_A0") (class "Default")
      (node (ref "IC1") (pin "5") (pinfunction "A0_5") (pintype "input"))
      (node (ref "U1") (pin "50") (pinfunction "PB16B_50") (pintype "passive"))
    )
    (net (code "102") (name "SRAM_A1") (class "Default")
      (node (ref "IC1") (pin "4") (pinfunction "A1_4") (pintype "input"))
      (node (ref "U1") (pin "49") (pinfunction "PB16A_49") (pintype "passive"))
    )
    (net (code "103") (name "SRAM_A2") (class "Default")
      (node (ref "IC1") (pin "3") (pinfunction "A2_3") (pintype "input"))
      (node (ref "U1") (pin "48") (pinfunction "PB13B_48") (pintype "passive"))
    )
    (net (code "104") (name "SRAM_A3") (class "Default")
      (node (ref "IC1") (pin "2") (pinfunction "A3_2") (pintype "input"))
      (node (ref "U1") (pin "47") (pinfunction "PB13A_47") (pintype "passive"))
    )
    (net (code "105") (name "SRAM_A4") (class "Default")
      (node (ref "IC1") (pin "1") (pinfunction "A4_1") (pintype "input"))
      (node (ref "U1") (pin "43") (pinfunction "PB9B_43") (pintype "passive"))
    )
    (net (code "106") (name "SRAM_A5") (class "Default")
      (node (ref "IC1") (pin "48") (pinfunction "A5_48") (pintype "input"))
      (node (ref "U1") (pin "73") (pinfunction "PR24B_73") (pintype "passive"))
    )
    (net (code "107") (name "SRAM_A6") (class "Default")
      (node (ref "IC1") (pin "47") (pinfunction "A6_47") (pintype "input"))
      (node (ref "U1") (pin "74") (pinfunction "PR24A_74") (pintype "passive"))
    )
    (net (code "108") (name "SRAM_A7") (class "Default")
      (node (ref "IC1") (pin "46") (pinfunction "A7_46") (pintype "input"))
      (node (ref "U1") (pin "75") (pinfunction "PR23B_75") (pintype "passive"))
    )
    (net (code "109") (name "SRAM_A8") (class "Default")
      (node (ref "IC1") (pin "45") (pinfunction "A8_45") (pintype "input"))
      (node (ref "U1") (pin "76") (pinfunction "PR23A_76") (pintype "passive"))
    )
    (net (code "110") (name "SRAM_A9") (class "Default")
      (node (ref "IC1") (pin "30") (pinfunction "A9_30") (pintype "input"))
      (node (ref "U1") (pin "92") (pinfunction "PR12A_92") (pintype "passive"))
    )
    (net (code "111") (name "SRAM_A10") (class "Default")
      (node (ref "IC1") (pin "29") (pinfunction "A10_29") (pintype "input"))
      (node (ref "U1") (pin "93") (pinfunction "PR11B_93") (pintype "passive"))
    )
    (net (code "112") (name "SRAM_A11") (class "Default")
      (node (ref "IC1") (pin "28") (pinfunction "A11_28") (pintype "input"))
      (node (ref "U1") (pin "94") (pinfunction "PR11A_94") (pintype "passive"))
    )
    (net (code "113") (name "SRAM_A12") (class "Default")
      (node (ref "IC1") (pin "27") (pinfunction "A12_27") (pintype "input"))
      (node (ref "U1") (pin "95") (pinfunction "PR9B_95") (pintype "passive"))
    )
    (net (code "114") (name "SRAM_A13") (class "Default")
      (node (ref "IC1") (pin "26") (pinfunction "A13_26") (pintype "input"))
      (node (ref "U1") (pin "96") (pinfunction "PR9A_96") (pintype "passive"))
    )
    (net (code "115") (name "SRAM_A14") (class "Default")
      (node (ref "IC1") (pin "25") (pinfunction "A14_25") (pintype "input"))
      (node (ref "U1") (pin "97") (pinfunction "PR7B_97") (pintype "passive"))
    )
    (net (code "116") (name "SRAM_A15") (class "Default")
      (node (ref "IC1") (pin "24") (pinfunction "A15_24") (pintype "input"))
      (node (ref "U1") (pin "69") (pinfunction "PB37B_69") (pintype "passive"))
    )
    (net (code "117") (name "SRAM_A16") (class "Default")
      (node (ref "IC1") (pin "23") (pinfunction "A16_23") (pintype "input"))
      (node (ref "U1") (pin "68") (pinfunction "PB37A_68") (pintype "passive"))
    )
    (net (code "118") (name "SRAM_A17") (class "Default")
      (node (ref "IC1") (pin "22") (pinfunction "A17_22") (pintype "input"))
      (node (ref "U1") (pin "67") (pinfunction "PB35B_67") (pintype "passive"))
    )
    (net (code "119") (name "SRAM_A18") (class "Default")
      (node (ref "IC1") (pin "21") (pinfunction "A18_21") (pintype "input"))
      (node (ref "U1") (pin "65") (pinfunction "PB35A_65") (pintype "passive"))
    )
    (net (code "120") (name "SRAM_A19") (class "Default")
      (node (ref "IC1") (pin "20") (pinfunction "A19_20") (pintype "input"))
      (node (ref "U1") (pin "63") (pinfunction "PB31D_63") (pintype "passive"))
    )
    (net (code "121") (name "SRAM_CE") (class "Default")
      (node (ref "IC1") (pin "7") (pinfunction "~{CE}_7") (pintype "input"))
      (node (ref "U1") (pin "52") (pinfunction "PB18A_52") (pintype "passive"))
    )
    (net (code "122") (name "SRAM_D0") (class "Default")
      (node (ref "IC1") (pin "8") (pinfunction "I/O0_8") (pintype "tri_state"))
      (node (ref "U1") (pin "54") (pinfunction "PB18B_54") (pintype "passive"))
    )
    (net (code "123") (name "SRAM_D1") (class "Default")
      (node (ref "IC1") (pin "9") (pinfunction "I/O1_9") (pintype "tri_state"))
      (node (ref "U1") (pin "55") (pinfunction "PB23A_55") (pintype "passive"))
    )
    (net (code "124") (name "SRAM_D2") (class "Default")
      (node (ref "IC1") (pin "10") (pinfunction "I/O2_10") (pintype "tri_state"))
      (node (ref "U1") (pin "56") (pinfunction "PB23B_56") (pintype "passive"))
    )
    (net (code "125") (name "SRAM_D3") (class "Default")
      (node (ref "IC1") (pin "11") (pinfunction "I/O3_11") (pintype "tri_state"))
      (node (ref "U1") (pin "57") (pinfunction "PB26A_57") (pintype "passive"))
    )
    (net (code "126") (name "SRAM_D4") (class "Default")
      (node (ref "IC1") (pin "14") (pinfunction "I/O4_14") (pintype "tri_state"))
      (node (ref "U1") (pin "58") (pinfunction "PB26B_58") (pintype "passive"))
    )
    (net (code "127") (name "SRAM_D5") (class "Default")
      (node (ref "IC1") (pin "15") (pinfunction "I/O5_15") (pintype "tri_state"))
      (node (ref "U1") (pin "59") (pinfunction "PB29A_59") (pintype "passive"))
    )
    (net (code "128") (name "SRAM_D6") (class "Default")
      (node (ref "IC1") (pin "16") (pinfunction "I/O6_16") (pintype "tri_state"))
      (node (ref "U1") (pin "60") (pinfunction "PB29B_60") (pintype "passive"))
    )
    (net (code "129") (name "SRAM_D7") (class "Default")
      (node (ref "IC1") (pin "17") (pinfunction "I/O7_17") (pintype "tri_state"))
      (node (ref "U1") (pin "61") (pinfunction "PB31A_61") (pintype "passive"))
    )
    (net (code "130") (name "SRAM_D8") (class "Default")
      (node (ref "IC1") (pin "32") (pinfunction "I/O8_32") (pintype "tri_state"))
      (node (ref "U1") (pin "91") (pinfunction "PR12B_91") (pintype "passive"))
    )
    (net (code "131") (name "SRAM_D9") (class "Default")
      (node (ref "IC1") (pin "33") (pinfunction "I/O9_33") (pintype "tri_state"))
      (node (ref "U1") (pin "89") (pinfunction "PR15A_89") (pintype "passive"))
    )
    (net (code "132") (name "SRAM_D10") (class "Default")
      (node (ref "IC1") (pin "34") (pinfunction "I/O10_34") (pintype "tri_state"))
      (node (ref "U1") (pin "87") (pinfunction "PR15B_87") (pintype "passive"))
    )
    (net (code "133") (name "SRAM_D11") (class "Default")
      (node (ref "IC1") (pin "35") (pinfunction "I/O11_35") (pintype "tri_state"))
      (node (ref "U1") (pin "86") (pinfunction "PR16A_86") (pintype "passive"))
    )
    (net (code "134") (name "SRAM_D12") (class "Default")
      (node (ref "IC1") (pin "38") (pinfunction "I/O12_38") (pintype "tri_state"))
      (node (ref "U1") (pin "85") (pinfunction "PR16B_85") (pintype "passive"))
    )
    (net (code "135") (name "SRAM_D13") (class "Default")
      (node (ref "IC1") (pin "39") (pinfunction "I/O13_39") (pintype "tri_state"))
      (node (ref "U1") (pin "84") (pinfunction "PR17A_84") (pintype "passive"))
    )
    (net (code "136") (name "SRAM_D14") (class "Default")
      (node (ref "IC1") (pin "40") (pinfunction "I/O14_40") (pintype "tri_state"))
      (node (ref "U1") (pin "83") (pinfunction "PR17B_83") (pintype "passive"))
    )
    (net (code "137") (name "SRAM_D15") (class "Default")
      (node (ref "IC1") (pin "41") (pinfunction "I/O15_41") (pintype "tri_state"))
      (node (ref "U1") (pin "82") (pinfunction "PR18A_82") (pintype "passive"))
    )
    (net (code "138") (name "SRAM_LB") (class "Default")
      (node (ref "IC1") (pin "42") (pinfunction "~{LB}_42") (pintype "input"))
      (node (ref "U1") (pin "81") (pinfunction "PR18B_81") (pintype "passive"))
    )
    (net (code "139") (name "SRAM_OE") (class "Default")
      (node (ref "IC1") (pin "44") (pinfunction "~{OE}_44") (pintype "input"))
      (node (ref "U1") (pin "77") (pinfunction "PR21B_77") (pintype "passive"))
    )
    (net (code "140") (name "SRAM_UB") (class "Default")
      (node (ref "IC1") (pin "43") (pinfunction "~{UB}_43") (pintype "input"))
      (node (ref "U1") (pin "78") (pinfunction "PR21A_78") (pintype "passive"))
    )
    (net (code "141") (name "SRAM_WE") (class "Default")
      (node (ref "IC1") (pin "18") (pinfunction "~{WE}_18") (pintype "input"))
      (node (ref "U1") (pin "62") (pinfunction "PB31B_62") (pintype "passive"))
    )
    (net (code "142") (name "USBAURT_TX") (class "Default")
      (node (ref "U$2") (pin "40") (pinfunction "BDBUS0_40") (pintype "output"))
      (node (ref "U1") (pin "133") (pinfunction "PT15A_133") (pintype "passive"))
    )
    (net (code "143") (name "USBJTAG_TCK") (class "Default")
      (node (ref "JP1") (pin "8") (pinfunction "8_8") (pintype "passive"))
      (node (ref "R14") (pin "2") (pinfunction "2_2") (pintype "passive"))
      (node (ref "U$2") (pin "24") (pinfunction "ADBUS0_24") (pintype "bidirectional"))
    )
    (net (code "144") (name "USBJTAG_TDI") (class "Default")
      (node (ref "JP1") (pin "6") (pinfunction "6_6") (pintype "passive"))
      (node (ref "R15") (pin "1") (pinfunction "1_1") (pintype "passive"))
      (node (ref "U$2") (pin "23") (pinfunction "ADBUS1_23") (pintype "bidirectional"))
    )
    (net (code "145") (name "USBJTAG_TDO") (class "Default")
      (node (ref "JP1") (pin "4") (pinfunction "4_4") (pintype "passive"))
      (node (ref "R16") (pin "1") (pinfunction "1_1") (pintype "passive"))
      (node (ref "U$2") (pin "22") (pinfunction "ADBUS2_22") (pintype "bidirectional"))
    )
    (net (code "146") (name "USBJTAG_TMS") (class "Default")
      (node (ref "JP1") (pin "10") (pinfunction "10_10") (pintype "passive"))
      (node (ref "R17") (pin "1") (pinfunction "1_1") (pintype "passive"))
      (node (ref "U$2") (pin "21") (pinfunction "ADBUS3_21") (pintype "bidirectional"))
    )
    (net (code "147") (name "USBUART_RX") (class "Default")
      (node (ref "U$2") (pin "39") (pinfunction "BDBUS1_39") (pintype "input"))
      (node (ref "U1") (pin "132") (pinfunction "PT15B_132") (pintype "passive"))
    )
    (net (code "148") (name "VID0") (class "Default")
      (node (ref "R41") (pin "1") (pinfunction "1_1") (pintype "passive"))
      (node (ref "U1") (pin "142") (pinfunction "PT9B_142") (pintype "passive"))
    )
    (net (code "149") (name "VID1") (class "Default")
      (node (ref "R40") (pin "1") (pinfunction "1_1") (pintype "passive"))
      (node (ref "U1") (pin "143") (pinfunction "PT9A_143") (pintype "passive"))
    )
    (net (code "150") (name "VID2") (class "Default")
      (node (ref "R39") (pin "1") (pinfunction "1_1") (pintype "passive"))
      (node (ref "U1") (pin "1") (pinfunction "PL3A_1") (pintype "passive"))
    )
    (net (code "151") (name "VID3") (class "Default")
      (node (ref "R36") (pin "1") (pinfunction "1_1") (pintype "passive"))
      (node (ref "U1") (pin "141") (pinfunction "PT10A_141") (pintype "passive"))
    )
    (net (code "152") (name "VID4") (class "Default")
      (node (ref "R35") (pin "1") (pinfunction "1_1") (pintype "passive"))
      (node (ref "U1") (pin "140") (pinfunction "PT10B_140") (pintype "passive"))
    )
    (net (code "153") (name "VID5") (class "Default")
      (node (ref "R34") (pin "1") (pinfunction "1_1") (pintype "passive"))
      (node (ref "U1") (pin "139") (pinfunction "PT11A_139") (pintype "passive"))
    )
    (net (code "154") (name "unconnected-(AUDIO-PadRSH)") (class "Default")
      (node (ref "AUDIO") (pin "RSH") (pinfunction "RSH_RSH") (pintype "bidirectional"))
    )
    (net (code "155") (name "unconnected-(AUDIO-PadTSH)") (class "Default")
      (node (ref "AUDIO") (pin "TSH") (pinfunction "TSH_TSH") (pintype "bidirectional"))
    )
    (net (code "156") (name "unconnected-(PS/2-Pad2)") (class "Default")
      (node (ref "PS/2") (pin "2") (pinfunction "2_2") (pintype "passive"))
    )
    (net (code "157") (name "unconnected-(PS/2-Pad6)") (class "Default")
      (node (ref "PS/2") (pin "6") (pinfunction "6_6") (pintype "passive"))
    )
    (net (code "158") (name "unconnected-(U$1-IR1Q,PIN8-Pad8)") (class "Default")
      (node (ref "U$1") (pin "8") (pinfunction "IR1Q,PIN8_8") (pintype "bidirectional"))
    )
    (net (code "159") (name "unconnected-(U$1-PIN9-Pad9)") (class "Default")
      (node (ref "U$1") (pin "9") (pinfunction "PIN9_9") (pintype "bidirectional"))
    )
    (net (code "160") (name "unconnected-(U$1-PadCD)") (class "Default")
      (node (ref "U$1") (pin "CD") (pinfunction "CD_CD") (pintype "bidirectional"))
    )
    (net (code "161") (name "unconnected-(U$1-PadWP)") (class "Default")
      (node (ref "U$1") (pin "WP") (pinfunction "WP_WP") (pintype "bidirectional"))
    )
    (net (code "162") (name "unconnected-(U$2-ACBUS0-Pad15)") (class "Default")
      (node (ref "U$2") (pin "15") (pinfunction "ACBUS0_15") (pintype "bidirectional"))
    )
    (net (code "163") (name "unconnected-(U$2-ACBUS1-Pad13)") (class "Default")
      (node (ref "U$2") (pin "13") (pinfunction "ACBUS1_13") (pintype "bidirectional"))
    )
    (net (code "164") (name "unconnected-(U$2-ACBUS2-Pad12)") (class "Default")
      (node (ref "U$2") (pin "12") (pinfunction "ACBUS2_12") (pintype "bidirectional"))
    )
    (net (code "165") (name "unconnected-(U$2-ACBUS3-Pad11)") (class "Default")
      (node (ref "U$2") (pin "11") (pinfunction "ACBUS3_11") (pintype "bidirectional"))
    )
    (net (code "166") (name "unconnected-(U$2-ADBUS4-Pad20)") (class "Default")
      (node (ref "U$2") (pin "20") (pinfunction "ADBUS4_20") (pintype "bidirectional"))
    )
    (net (code "167") (name "unconnected-(U$2-ADBUS5-Pad19)") (class "Default")
      (node (ref "U$2") (pin "19") (pinfunction "ADBUS5_19") (pintype "bidirectional"))
    )
    (net (code "168") (name "unconnected-(U$2-ADBUS6-Pad17)") (class "Default")
      (node (ref "U$2") (pin "17") (pinfunction "ADBUS6_17") (pintype "bidirectional"))
    )
    (net (code "169") (name "unconnected-(U$2-ADBUS7-Pad16)") (class "Default")
      (node (ref "U$2") (pin "16") (pinfunction "ADBUS7_16") (pintype "bidirectional"))
    )
    (net (code "170") (name "unconnected-(U$2-BCBUS0-Pad30)") (class "Default")
      (node (ref "U$2") (pin "30") (pinfunction "BCBUS0_30") (pintype "bidirectional"))
    )
    (net (code "171") (name "unconnected-(U$2-BCBUS1-Pad29)") (class "Default")
      (node (ref "U$2") (pin "29") (pinfunction "BCBUS1_29") (pintype "bidirectional"))
    )
    (net (code "172") (name "unconnected-(U$2-BCBUS2-Pad28)") (class "Default")
      (node (ref "U$2") (pin "28") (pinfunction "BCBUS2_28") (pintype "bidirectional"))
    )
    (net (code "173") (name "unconnected-(U$2-BCBUS3-Pad27)") (class "Default")
      (node (ref "U$2") (pin "27") (pinfunction "BCBUS3_27") (pintype "bidirectional"))
    )
    (net (code "174") (name "unconnected-(U$2-BDBUS2-Pad38)") (class "Default")
      (node (ref "U$2") (pin "38") (pinfunction "BDBUS2_38") (pintype "output"))
    )
    (net (code "175") (name "unconnected-(U$2-BDBUS3-Pad37)") (class "Default")
      (node (ref "U$2") (pin "37") (pinfunction "BDBUS3_37") (pintype "input"))
    )
    (net (code "176") (name "unconnected-(U$2-BDBUS4-Pad36)") (class "Default")
      (node (ref "U$2") (pin "36") (pinfunction "BDBUS4_36") (pintype "output"))
    )
    (net (code "177") (name "unconnected-(U$2-BDBUS5-Pad35)") (class "Default")
      (node (ref "U$2") (pin "35") (pinfunction "BDBUS5_35") (pintype "input"))
    )
    (net (code "178") (name "unconnected-(U$2-BDBUS6-Pad33)") (class "Default")
      (node (ref "U$2") (pin "33") (pinfunction "BDBUS6_33") (pintype "input"))
    )
    (net (code "179") (name "unconnected-(U$2-BDBUS7-Pad32)") (class "Default")
      (node (ref "U$2") (pin "32") (pinfunction "BDBUS7_32") (pintype "input"))
    )
    (net (code "180") (name "unconnected-(U$2-EECS-Pad48)") (class "Default")
      (node (ref "U$2") (pin "48") (pinfunction "EECS_48") (pintype "bidirectional"))
    )
    (net (code "181") (name "unconnected-(U$2-EESK-Pad1)") (class "Default")
      (node (ref "U$2") (pin "1") (pinfunction "EESK_1") (pintype "bidirectional"))
    )
    (net (code "182") (name "unconnected-(U$2-PWEN#-Pad41)") (class "Default")
      (node (ref "U$2") (pin "41") (pinfunction "PWEN#_41") (pintype "bidirectional"))
    )
    (net (code "183") (name "unconnected-(U$2-SI{slash}WUA-Pad10)") (class "Default")
      (node (ref "U$2") (pin "10") (pinfunction "SI/WUA_10") (pintype "bidirectional"))
    )
    (net (code "184") (name "unconnected-(U$2-SI{slash}WUB-Pad26)") (class "Default")
      (node (ref "U$2") (pin "26") (pinfunction "SI/WUB_26") (pintype "bidirectional"))
    )
    (net (code "185") (name "unconnected-(U1B-NC-Pad129)") (class "Default")
      (node (ref "U1") (pin "129") (pinfunction "NC_129") (pintype "no_connect"))
    )
    (net (code "186") (name "unconnected-(U2-USBID-PadID1)") (class "Default")
      (node (ref "U2") (pin "ID1") (pinfunction "USBID_ID1") (pintype "bidirectional"))
    )
  )
)
